# arduinoVisor4.net
KiCad netlist of a schematic drawn in EAGLE
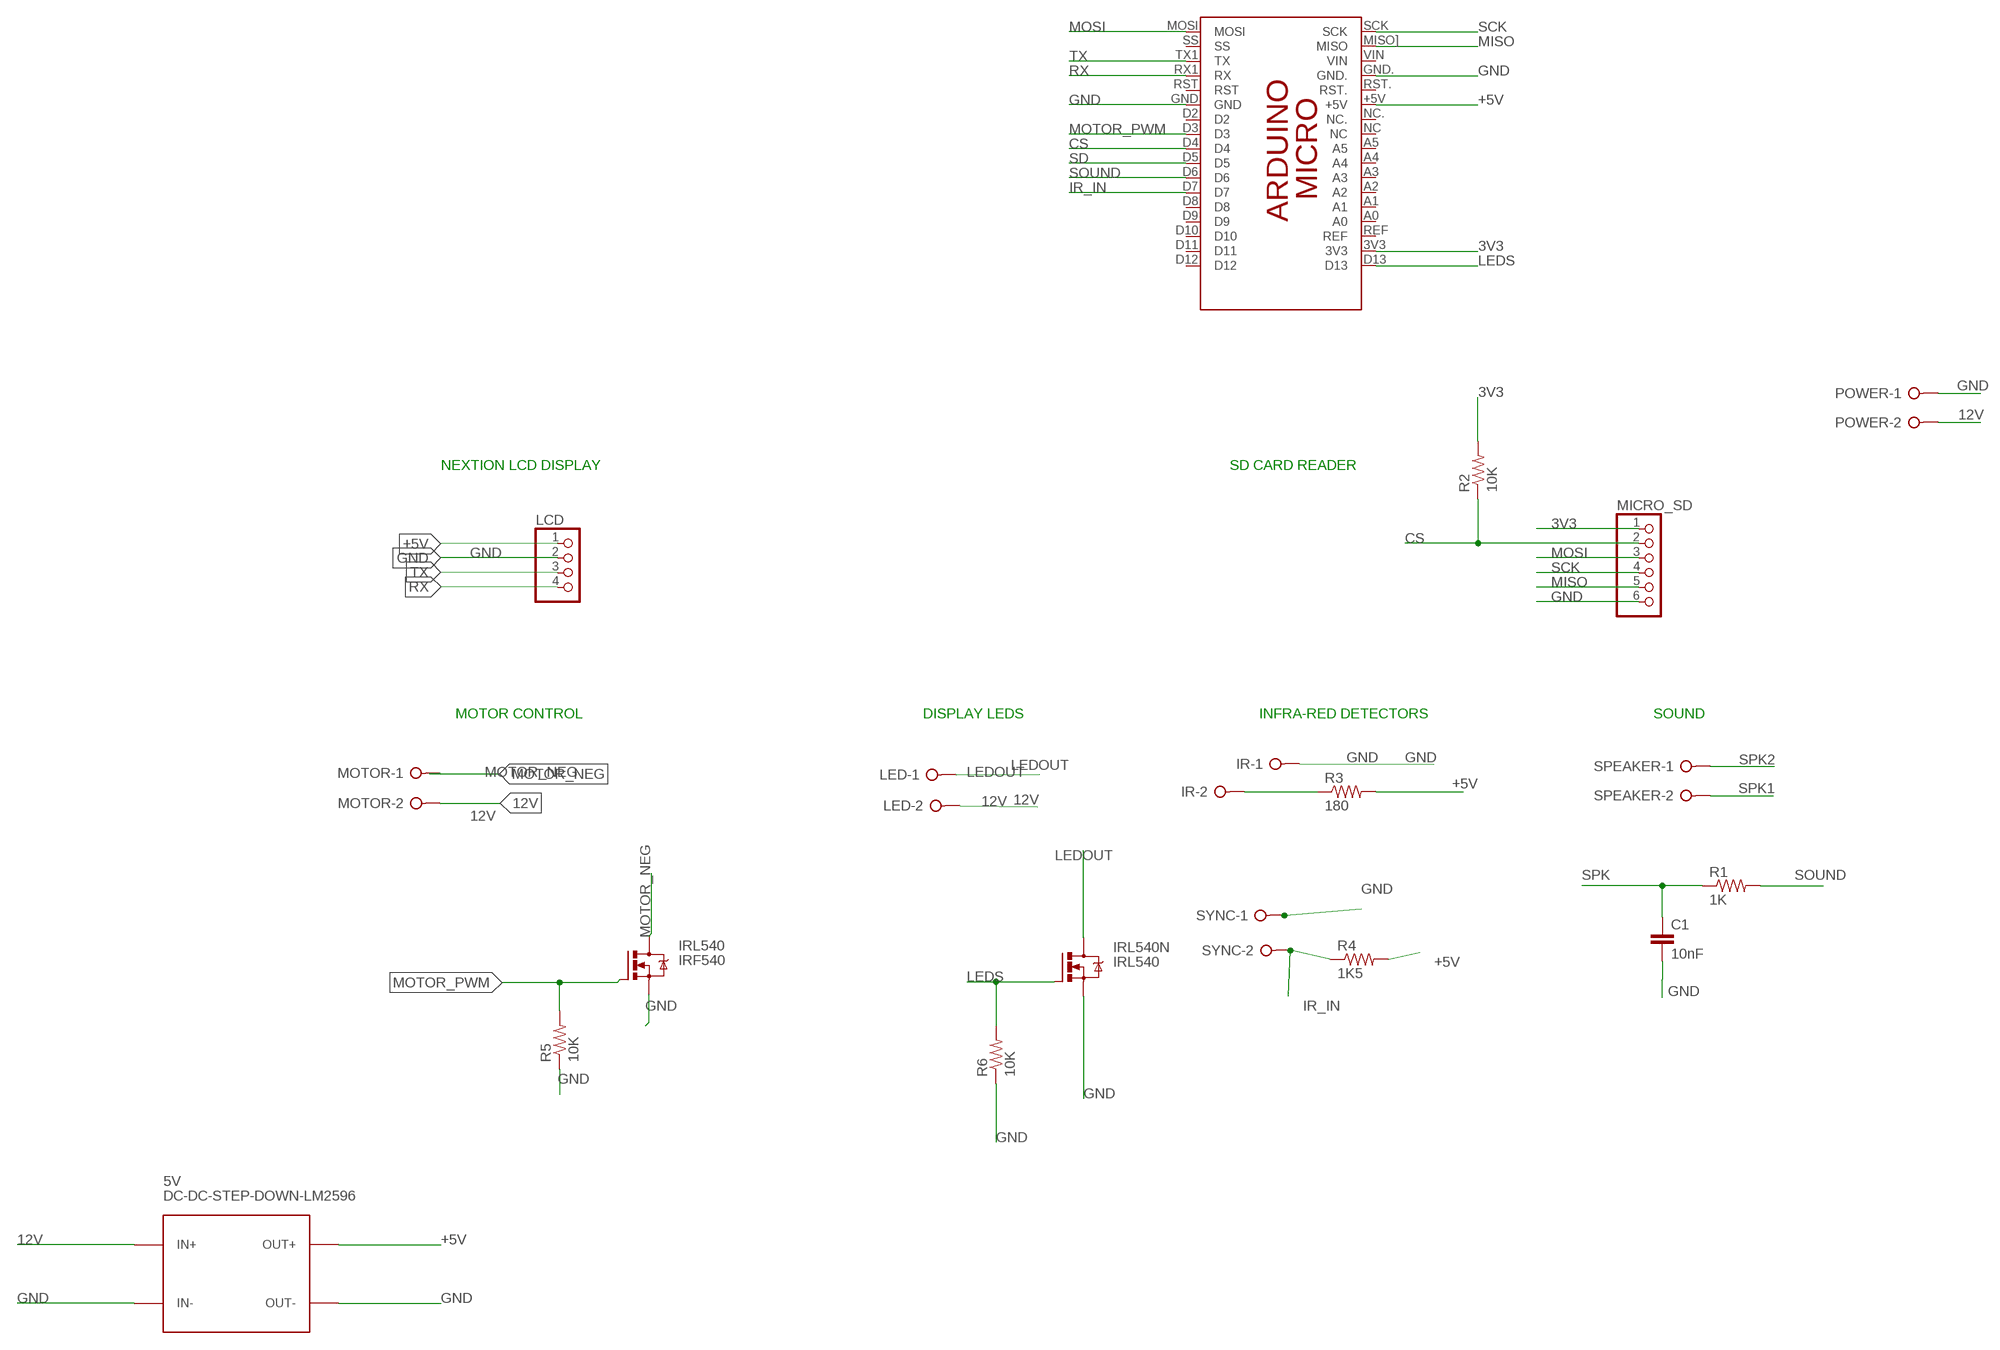
[diagram p0: schematic, sheet 1]
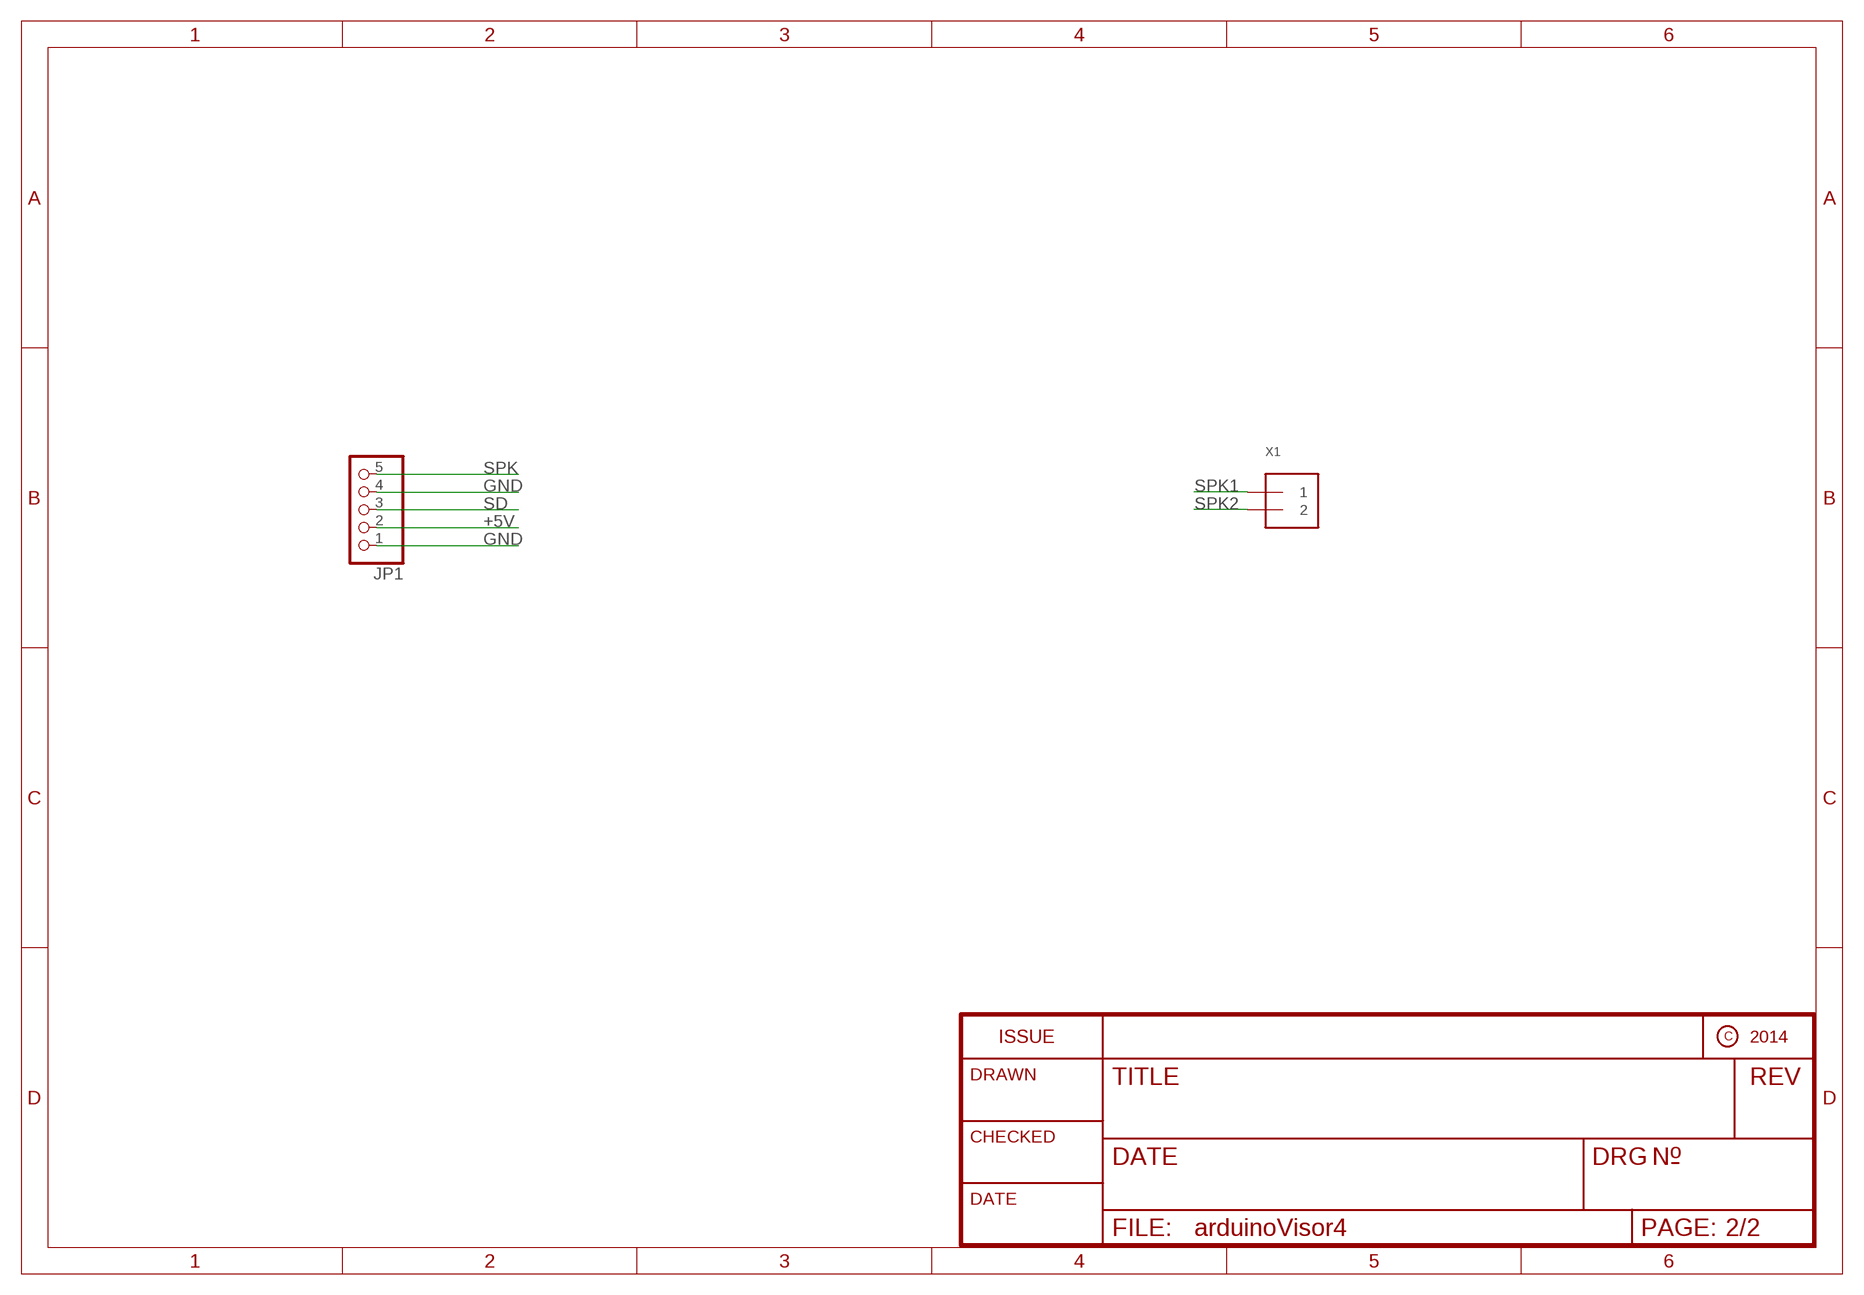
[diagram p1: schematic, sheet 2]

(export (version "E")
  (design (tool "Eeschema 10.0.6"))
  (components
    (comp (ref "5V")
      (value "DC-DC-STEP-DOWN-LM2596")
      (footprint "eagle-import:DC-DC-STEP-DOWN-LM2596")
      (libsource (lib "eagle-import") (part "DC-DC-STEP-DOWN-LM2596"))
    )
    (comp (ref "C1")
      (value "10nF")
      (footprint "eagle-import:C2.5-2")
      (libsource (lib "eagle-import") (part "C2.5/2"))
    )
    (comp (ref "IR")
      (value "W237-02P")
      (footprint "eagle-import:W237-132")
      (libsource (lib "eagle-import") (part "W237-02P"))
    )
    (comp (ref "IRL540")
      (value "IRF540")
      (footprint "eagle-import:TO220BV")
      (libsource (lib "eagle-import") (part "IRF540"))
    )
    (comp (ref "IRL540N")
      (value "IRL540")
      (footprint "eagle-import:TO220BV")
      (libsource (lib "eagle-import") (part "IRF540"))
    )
    (comp (ref "LCD")
      (value "PINHD-1X4")
      (footprint "eagle-import:1X04")
      (libsource (lib "eagle-import") (part "PINHD-1X4"))
    )
    (comp (ref "LED")
      (value "W237-02P")
      (footprint "eagle-import:W237-132")
      (libsource (lib "eagle-import") (part "W237-02P"))
    )
    (comp (ref "MICRO_SD")
      (value "PINHD-1X6")
      (footprint "eagle-import:1X06")
      (libsource (lib "eagle-import") (part "PINHD-1X6"))
    )
    (comp (ref "MOTOR")
      (value "W237-02P")
      (footprint "eagle-import:W237-132")
      (libsource (lib "eagle-import") (part "W237-02P"))
    )
    (comp (ref "PCB2")
      (value "ARDUINO_MICRO")
      (footprint "eagle-import:ARDUINO_MICRO")
      (libsource (lib "eagle-import") (part "ARDUINO_MICRO"))
    )
    (comp (ref "POWER")
      (value "W237-02P")
      (footprint "eagle-import:W237-132")
      (libsource (lib "eagle-import") (part "W237-02P"))
    )
    (comp (ref "R1")
      (value "1K")
      (footprint "eagle-import:0207_10")
      (libsource (lib "eagle-import") (part "R-US_0207/10"))
    )
    (comp (ref "R2")
      (value "10K")
      (footprint "eagle-import:0207_10")
      (libsource (lib "eagle-import") (part "R-US_0207/10"))
    )
    (comp (ref "R3")
      (value "180")
      (footprint "eagle-import:0207_10")
      (libsource (lib "eagle-import") (part "R-US_0207/10"))
    )
    (comp (ref "R4")
      (value "1K5")
      (footprint "eagle-import:0207_10")
      (libsource (lib "eagle-import") (part "R-US_0207/10"))
    )
    (comp (ref "R5")
      (value "10K")
      (footprint "eagle-import:0207_10")
      (libsource (lib "eagle-import") (part "R-US_0207/10"))
    )
    (comp (ref "R6")
      (value "10K")
      (footprint "eagle-import:0207_10")
      (libsource (lib "eagle-import") (part "R-US_0207/10"))
    )
    (comp (ref "SPEAKER")
      (value "W237-02P")
      (footprint "eagle-import:W237-132")
      (libsource (lib "eagle-import") (part "W237-02P"))
    )
    (comp (ref "SYNC")
      (value "W237-02P")
      (footprint "eagle-import:W237-132")
      (libsource (lib "eagle-import") (part "W237-02P"))
    )
    (comp (ref "JP1")
      (value "HEADER-1X570MIL")
      (footprint "eagle-import:1X05_ROUND_70")
      (libsource (lib "eagle-import") (part "HEADER-1X570MIL"))
    )
    (comp (ref "X1")
      (value "TERMBLOCK_1X2")
      (footprint "eagle-import:TERMBLOCK_1X2-3.5MM")
      (libsource (lib "eagle-import") (part "TERMBLOCK_1X2"))
    )
  )
  (nets
    (net (code "1") (name "+5V") (class "Default")
      (node (ref "5V") (pin "OUT+") (pinfunction "OUT+_OUT+") (pintype "bidirectional"))
      (node (ref "JP1") (pin "2") (pinfunction "2_2") (pintype "passive"))
      (node (ref "LCD") (pin "1") (pinfunction "1_1") (pintype "passive"))
      (node (ref "PCB2") (pin "+5V") (pinfunction "+5V_+5V") (pintype "bidirectional"))
      (node (ref "R3") (pin "2") (pinfunction "2_2") (pintype "passive"))
      (node (ref "R4") (pin "2") (pinfunction "2_2") (pintype "passive"))
    )
    (net (code "2") (name "3V3") (class "Default")
      (node (ref "MICRO_SD") (pin "1") (pinfunction "1_1") (pintype "passive"))
      (node (ref "PCB2") (pin "3V3") (pinfunction "3V3_3V3") (pintype "bidirectional"))
      (node (ref "R2") (pin "2") (pinfunction "2_2") (pintype "passive"))
    )
    (net (code "3") (name "12V") (class "Default")
      (node (ref "5V") (pin "IN+") (pinfunction "IN+_IN+") (pintype "bidirectional"))
      (node (ref "LED") (pin "2") (pinfunction "KL_2") (pintype "passive"))
      (node (ref "MOTOR") (pin "2") (pinfunction "KL_2") (pintype "passive"))
      (node (ref "POWER") (pin "2") (pinfunction "KL_2") (pintype "passive"))
    )
    (net (code "4") (name "CS") (class "Default")
      (node (ref "MICRO_SD") (pin "2") (pinfunction "2_2") (pintype "passive"))
      (node (ref "PCB2") (pin "D4") (pinfunction "D4_D4") (pintype "bidirectional"))
      (node (ref "R2") (pin "1") (pinfunction "1_1") (pintype "passive"))
    )
    (net (code "5") (name "GND") (class "Default")
      (node (ref "5V") (pin "IN-") (pinfunction "IN-_IN-") (pintype "bidirectional"))
      (node (ref "5V") (pin "OUT-") (pinfunction "OUT-_OUT-") (pintype "bidirectional"))
      (node (ref "C1") (pin "2") (pinfunction "2_2") (pintype "passive"))
      (node (ref "IR") (pin "1") (pinfunction "KL_1") (pintype "passive"))
      (node (ref "IRL540") (pin "S") (pinfunction "S_S") (pintype "passive"))
      (node (ref "IRL540N") (pin "S") (pinfunction "S_S") (pintype "passive"))
      (node (ref "JP1") (pin "1") (pinfunction "1_1") (pintype "passive"))
      (node (ref "JP1") (pin "4") (pinfunction "4_4") (pintype "passive"))
      (node (ref "LCD") (pin "2") (pinfunction "2_2") (pintype "passive"))
      (node (ref "MICRO_SD") (pin "6") (pinfunction "6_6") (pintype "passive"))
      (node (ref "PCB2") (pin "GND") (pinfunction "GND_GND") (pintype "bidirectional"))
      (node (ref "PCB2") (pin "GND.") (pinfunction "GND._GND.") (pintype "bidirectional"))
      (node (ref "POWER") (pin "1") (pinfunction "KL_1") (pintype "passive"))
      (node (ref "R5") (pin "1") (pinfunction "1_1") (pintype "passive"))
      (node (ref "R6") (pin "1") (pinfunction "1_1") (pintype "passive"))
      (node (ref "SYNC") (pin "1") (pinfunction "KL_1") (pintype "passive"))
    )
    (net (code "6") (name "IR_IN") (class "Default")
      (node (ref "PCB2") (pin "D7") (pinfunction "D7_D7") (pintype "bidirectional"))
      (node (ref "R4") (pin "1") (pinfunction "1_1") (pintype "passive"))
      (node (ref "SYNC") (pin "2") (pinfunction "KL_2") (pintype "passive"))
    )
    (net (code "7") (name "LEDOUT") (class "Default")
      (node (ref "IRL540N") (pin "D") (pinfunction "D_D") (pintype "passive"))
      (node (ref "LED") (pin "1") (pinfunction "KL_1") (pintype "passive"))
    )
    (net (code "8") (name "LEDS") (class "Default")
      (node (ref "IRL540N") (pin "G") (pinfunction "G_G") (pintype "passive"))
      (node (ref "PCB2") (pin "D13") (pinfunction "D13_D13") (pintype "bidirectional"))
      (node (ref "R6") (pin "2") (pinfunction "2_2") (pintype "passive"))
    )
    (net (code "9") (name "MISO") (class "Default")
      (node (ref "MICRO_SD") (pin "5") (pinfunction "5_5") (pintype "passive"))
      (node (ref "PCB2") (pin "MISO]") (pinfunction "MISO_MISO]") (pintype "bidirectional"))
    )
    (net (code "10") (name "MOSI") (class "Default")
      (node (ref "MICRO_SD") (pin "3") (pinfunction "3_3") (pintype "passive"))
      (node (ref "PCB2") (pin "MOSI") (pinfunction "MOSI_MOSI") (pintype "bidirectional"))
    )
    (net (code "11") (name "MOTOR_NEG") (class "Default")
      (node (ref "IRL540") (pin "D") (pinfunction "D_D") (pintype "passive"))
      (node (ref "MOTOR") (pin "1") (pinfunction "KL_1") (pintype "passive"))
    )
    (net (code "12") (name "MOTOR_PWM") (class "Default")
      (node (ref "IRL540") (pin "G") (pinfunction "G_G") (pintype "passive"))
      (node (ref "PCB2") (pin "D3") (pinfunction "D3_D3") (pintype "bidirectional"))
      (node (ref "R5") (pin "2") (pinfunction "2_2") (pintype "passive"))
    )
    (net (code "13") (name "Net-(IRB-KL)") (class "Default")
      (node (ref "IR") (pin "2") (pinfunction "KL_2") (pintype "passive"))
      (node (ref "R3") (pin "1") (pinfunction "1_1") (pintype "passive"))
    )
    (net (code "14") (name "RX") (class "Default")
      (node (ref "LCD") (pin "4") (pinfunction "4_4") (pintype "passive"))
      (node (ref "PCB2") (pin "RX1") (pinfunction "RX_RX1") (pintype "bidirectional"))
    )
    (net (code "15") (name "SCK") (class "Default")
      (node (ref "MICRO_SD") (pin "4") (pinfunction "4_4") (pintype "passive"))
      (node (ref "PCB2") (pin "SCK") (pinfunction "SCK_SCK") (pintype "bidirectional"))
    )
    (net (code "16") (name "SD") (class "Default")
      (node (ref "JP1") (pin "3") (pinfunction "3_3") (pintype "passive"))
      (node (ref "PCB2") (pin "D5") (pinfunction "D5_D5") (pintype "bidirectional"))
    )
    (net (code "17") (name "SOUND") (class "Default")
      (node (ref "PCB2") (pin "D6") (pinfunction "D6_D6") (pintype "bidirectional"))
      (node (ref "R1") (pin "2") (pinfunction "2_2") (pintype "passive"))
    )
    (net (code "18") (name "SPK") (class "Default")
      (node (ref "C1") (pin "1") (pinfunction "1_1") (pintype "passive"))
      (node (ref "JP1") (pin "5") (pinfunction "5_5") (pintype "passive"))
      (node (ref "R1") (pin "1") (pinfunction "1_1") (pintype "passive"))
    )
    (net (code "19") (name "SPK1") (class "Default")
      (node (ref "SPEAKER") (pin "2") (pinfunction "KL_2") (pintype "passive"))
      (node (ref "X1") (pin "1") (pinfunction "1_1") (pintype "passive"))
    )
    (net (code "20") (name "SPK2") (class "Default")
      (node (ref "SPEAKER") (pin "1") (pinfunction "KL_1") (pintype "passive"))
      (node (ref "X1") (pin "2") (pinfunction "2_2") (pintype "passive"))
    )
    (net (code "21") (name "TX") (class "Default")
      (node (ref "LCD") (pin "3") (pinfunction "3_3") (pintype "passive"))
      (node (ref "PCB2") (pin "TX1") (pinfunction "TX_TX1") (pintype "bidirectional"))
    )
    (net (code "22") (name "unconnected-(PCB2-PadA0)") (class "Default")
      (node (ref "PCB2") (pin "A0") (pinfunction "A0_A0") (pintype "bidirectional"))
    )
    (net (code "23") (name "unconnected-(PCB2-PadA1)") (class "Default")
      (node (ref "PCB2") (pin "A1") (pinfunction "A1_A1") (pintype "bidirectional"))
    )
    (net (code "24") (name "unconnected-(PCB2-PadA2)") (class "Default")
      (node (ref "PCB2") (pin "A2") (pinfunction "A2_A2") (pintype "bidirectional"))
    )
    (net (code "25") (name "unconnected-(PCB2-PadA3)") (class "Default")
      (node (ref "PCB2") (pin "A3") (pinfunction "A3_A3") (pintype "bidirectional"))
    )
    (net (code "26") (name "unconnected-(PCB2-PadA4)") (class "Default")
      (node (ref "PCB2") (pin "A4") (pinfunction "A4_A4") (pintype "bidirectional"))
    )
    (net (code "27") (name "unconnected-(PCB2-PadA5)") (class "Default")
      (node (ref "PCB2") (pin "A5") (pinfunction "A5_A5") (pintype "bidirectional"))
    )
    (net (code "28") (name "unconnected-(PCB2-PadD2)") (class "Default")
      (node (ref "PCB2") (pin "D2") (pinfunction "D2_D2") (pintype "bidirectional"))
    )
    (net (code "29") (name "unconnected-(PCB2-PadD8)") (class "Default")
      (node (ref "PCB2") (pin "D8") (pinfunction "D8_D8") (pintype "bidirectional"))
    )
    (net (code "30") (name "unconnected-(PCB2-PadD9)") (class "Default")
      (node (ref "PCB2") (pin "D9") (pinfunction "D9_D9") (pintype "bidirectional"))
    )
    (net (code "31") (name "unconnected-(PCB2-PadD10)") (class "Default")
      (node (ref "PCB2") (pin "D10") (pinfunction "D10_D10") (pintype "bidirectional"))
    )
    (net (code "32") (name "unconnected-(PCB2-PadD11)") (class "Default")
      (node (ref "PCB2") (pin "D11") (pinfunction "D11_D11") (pintype "bidirectional"))
    )
    (net (code "33") (name "unconnected-(PCB2-PadD12)") (class "Default")
      (node (ref "PCB2") (pin "D12") (pinfunction "D12_D12") (pintype "bidirectional"))
    )
    (net (code "34") (name "unconnected-(PCB2-PadNC)") (class "Default")
      (node (ref "PCB2") (pin "NC") (pinfunction "NC_NC") (pintype "bidirectional"))
    )
    (net (code "35") (name "unconnected-(PCB2-PadNC.)") (class "Default")
      (node (ref "PCB2") (pin "NC.") (pinfunction "NC._NC.") (pintype "bidirectional"))
    )
    (net (code "36") (name "unconnected-(PCB2-PadREF)") (class "Default")
      (node (ref "PCB2") (pin "REF") (pinfunction "REF_REF") (pintype "bidirectional"))
    )
    (net (code "37") (name "unconnected-(PCB2-PadRST)") (class "Default")
      (node (ref "PCB2") (pin "RST") (pinfunction "RST_RST") (pintype "bidirectional"))
    )
    (net (code "38") (name "unconnected-(PCB2-PadRST.)") (class "Default")
      (node (ref "PCB2") (pin "RST.") (pinfunction "RST._RST.") (pintype "bidirectional"))
    )
    (net (code "39") (name "unconnected-(PCB2-PadSS)") (class "Default")
      (node (ref "PCB2") (pin "SS") (pinfunction "SS_SS") (pintype "bidirectional"))
    )
    (net (code "40") (name "unconnected-(PCB2-PadVIN)") (class "Default")
      (node (ref "PCB2") (pin "VIN") (pinfunction "VIN_VIN") (pintype "bidirectional"))
    )
  )
)
